# SCH_5v3a-lmr51430_2023-02-02.net
KiCad netlist of a schematic drawn in EasyEDA
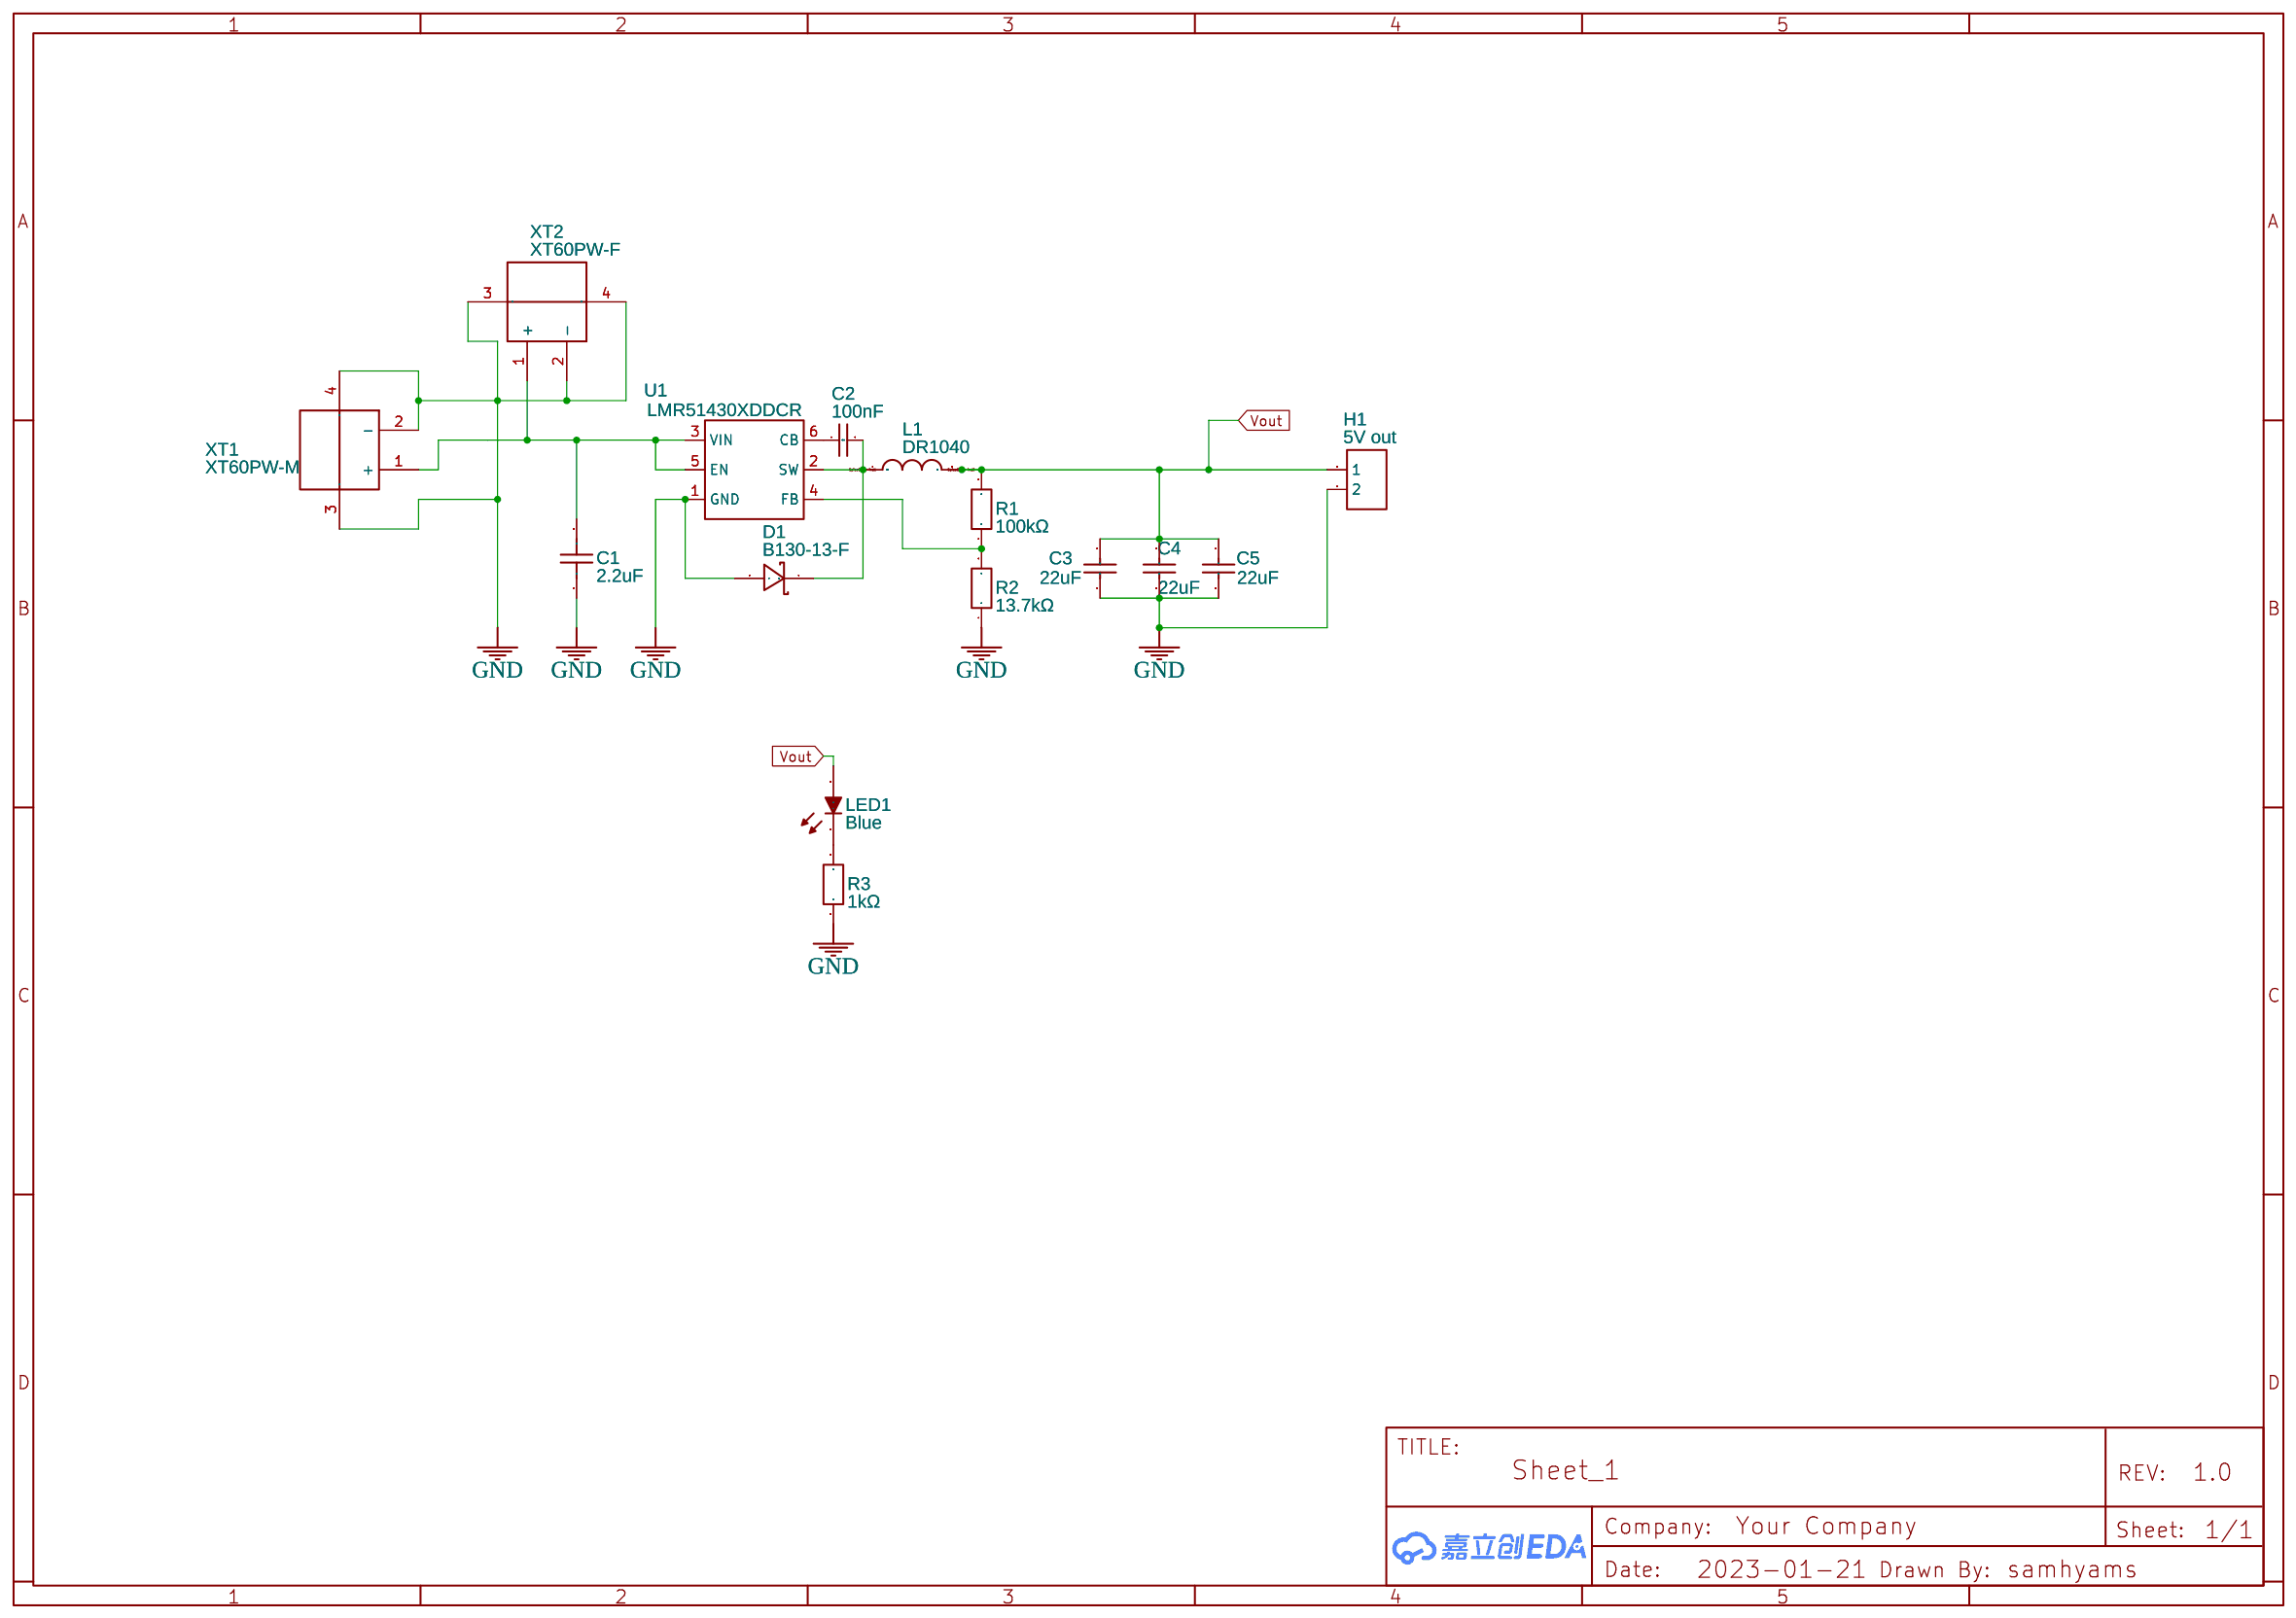
[diagram p0: schematic sheet]

(export (version "E")
  (design (tool "Eeschema 10.0.6"))
  (components
    (comp (ref "C1")
      (value "2.2uF")
      (fields
        (field (name "BOM_Manufacturer Part") "CL21B225KBYNNWE")
        (field (name "BOM_Supplier Part") "187-CL21B225KBYNNWE")
      )
      (libsource (lib "") (part "2.2uF 0805 50 VDC"))
    )
    (comp (ref "C2")
      (value "100nF")
      (fields
        (field (name "BOM_Manufacturer Part") "CL10B104KB8NNNC")
        (field (name "BOM_Supplier Part") "C1591")
      )
      (libsource (lib "") (part "100nF CL10B104KB8NNNC"))
    )
    (comp (ref "C3")
      (value "22uF")
      (fields
        (field (name "BOM_Manufacturer Part") "CL21A226MPQNNNE")
        (field (name "BOM_Supplier Part") "C29277")
      )
      (libsource (lib "") (part "CL21A226MPQNNNE"))
    )
    (comp (ref "C4")
      (value "22uF")
      (fields
        (field (name "BOM_Manufacturer Part") "CL21A226MPQNNNE")
        (field (name "BOM_Supplier Part") "C29277")
      )
      (libsource (lib "") (part "CL21A226MPQNNNE"))
    )
    (comp (ref "C5")
      (value "22uF")
      (fields
        (field (name "BOM_Manufacturer Part") "CL21A226MPQNNNE")
        (field (name "BOM_Supplier Part") "C29277")
      )
      (libsource (lib "") (part "CL21A226MPQNNNE"))
    )
    (comp (ref "D1")
      (value "B130-13-F")
      (fields (field (name "BOM_Supplier Part") "C134423"))
      (libsource (lib "") (part "B130-13-F"))
    )
    (comp (ref "H1")
      (value "5V out")
      (fields (field (name "BOM_Supplier Part") "C49661"))
      (libsource (lib "") (part "HDR-F-2.54_1x2"))
    )
    (comp (ref "L1") (value "DR1040") (libsource (lib "") (part "INDUCT-DR1040")))
    (comp (ref "LED1")
      (value "Blue")
      (fields
        (field (name "BOM_Manufacturer Part") "LED EL 0603 RT")
        (field (name "BOM_Supplier Part") "19-213/R6C-AQ1R2B/3T")
      )
      (libsource (lib "") (part "LED0603"))
    )
    (comp (ref "R1")
      (value "100kΩ")
      (fields
        (field (name "BOM_Manufacturer Part") "ERJ-1GEF1003C")
        (field (name "BOM_Supplier Part") "C2096564")
      )
      (libsource (lib "") (part "ERJ-1GEF1003C"))
    )
    (comp (ref "R2")
      (value "13.7kΩ")
      (fields
        (field (name "BOM_Manufacturer Part") "ERJ-1GEF1003C")
        (field (name "BOM_Supplier Part") "C2096564")
      )
      (libsource (lib "") (part "ERJ-1GEF1003C"))
    )
    (comp (ref "R3")
      (value "1kΩ")
      (fields
        (field (name "BOM_Manufacturer Part") "RMCF0402FT499R")
        (field (name "BOM_Supplier Part") "C9900006875")
      )
      (libsource (lib "") (part "RMCF0402FT499R"))
    )
    (comp (ref "U1")
      (value "LMR51430XDDCR")
      (fields (field (name "BOM_Supplier Part") "C5185863"))
      (libsource (lib "") (part "LMR51430XDDCR"))
    )
    (comp (ref "XT1")
      (value "XT60PW-M")
      (fields (field (name "BOM_Supplier Part") "C98732"))
      (libsource (lib "") (part "XT60PW-M"))
    )
    (comp (ref "XT2") (value "XT60PW-F") (libsource (lib "") (part "XT60PW-F")))
  )
  (nets
    (net (code "1") (name "GND") (class "Default")
      (node (ref "C1") (pin "1") (pinfunction "1_1") (pintype "unspecified"))
      (node (ref "C3") (pin "1") (pinfunction "1_1") (pintype "input"))
      (node (ref "C4") (pin "1") (pinfunction "1_1") (pintype "input"))
      (node (ref "C5") (pin "1") (pinfunction "1_1") (pintype "input"))
      (node (ref "D1") (pin "2") (pinfunction "A_2") (pintype "unspecified"))
      (node (ref "H1") (pin "2") (pinfunction "2_2") (pintype "input"))
      (node (ref "R2") (pin "1") (pinfunction "1_1") (pintype "unspecified"))
      (node (ref "R3") (pin "1") (pinfunction "1_1") (pintype "unspecified"))
      (node (ref "U1") (pin "1") (pinfunction "GND_1") (pintype "unspecified"))
      (node (ref "XT1") (pin "2") (pinfunction "-_2") (pintype "unspecified"))
      (node (ref "XT1") (pin "3") (pinfunction "NA_3") (pintype "unspecified"))
      (node (ref "XT1") (pin "4") (pinfunction "NA_4") (pintype "unspecified"))
      (node (ref "XT2") (pin "2") (pinfunction "-_2") (pintype "unspecified"))
      (node (ref "XT2") (pin "3") (pinfunction "NA_3") (pintype "unspecified"))
      (node (ref "XT2") (pin "4") (pinfunction "NA_4") (pintype "unspecified"))
    )
    (net (code "2") (name "Net-(D1-C)") (class "Default")
      (node (ref "C2") (pin "2") (pinfunction "2_2") (pintype "unspecified"))
      (node (ref "D1") (pin "1") (pinfunction "C_1") (pintype "unspecified"))
      (node (ref "L1") (pin "1") (pinfunction "P$1_1") (pintype "bidirectional"))
      (node (ref "U1") (pin "2") (pinfunction "SW_2") (pintype "unspecified"))
    )
    (net (code "3") (name "Net-(LED1--)") (class "Default")
      (node (ref "LED1") (pin "2") (pinfunction "-_2") (pintype "unspecified"))
      (node (ref "R3") (pin "2") (pinfunction "2_2") (pintype "unspecified"))
    )
    (net (code "4") (name "Net-(U1-CB)") (class "Default")
      (node (ref "C2") (pin "1") (pinfunction "1_1") (pintype "unspecified"))
      (node (ref "U1") (pin "6") (pinfunction "CB_6") (pintype "unspecified"))
    )
    (net (code "5") (name "Net-(U1-EN)") (class "Default")
      (node (ref "C1") (pin "2") (pinfunction "2_2") (pintype "unspecified"))
      (node (ref "U1") (pin "3") (pinfunction "VIN_3") (pintype "unspecified"))
      (node (ref "U1") (pin "5") (pinfunction "EN_5") (pintype "unspecified"))
      (node (ref "XT1") (pin "1") (pinfunction "+_1") (pintype "unspecified"))
      (node (ref "XT2") (pin "1") (pinfunction "+_1") (pintype "unspecified"))
    )
    (net (code "6") (name "Net-(U1-FB)") (class "Default")
      (node (ref "R1") (pin "1") (pinfunction "1_1") (pintype "unspecified"))
      (node (ref "R2") (pin "2") (pinfunction "2_2") (pintype "unspecified"))
      (node (ref "U1") (pin "4") (pinfunction "FB_4") (pintype "unspecified"))
    )
    (net (code "7") (name "Vout") (class "Default")
      (node (ref "C3") (pin "2") (pinfunction "2_2") (pintype "input"))
      (node (ref "C4") (pin "2") (pinfunction "2_2") (pintype "input"))
      (node (ref "C5") (pin "2") (pinfunction "2_2") (pintype "input"))
      (node (ref "H1") (pin "1") (pinfunction "1_1") (pintype "input"))
      (node (ref "L1") (pin "2") (pinfunction "P$2_2") (pintype "bidirectional"))
      (node (ref "LED1") (pin "1") (pinfunction "+_1") (pintype "unspecified"))
      (node (ref "R1") (pin "2") (pinfunction "2_2") (pintype "unspecified"))
    )
  )
)
